# catt.net
KiCad netlist of a schematic drawn in Altium Designer
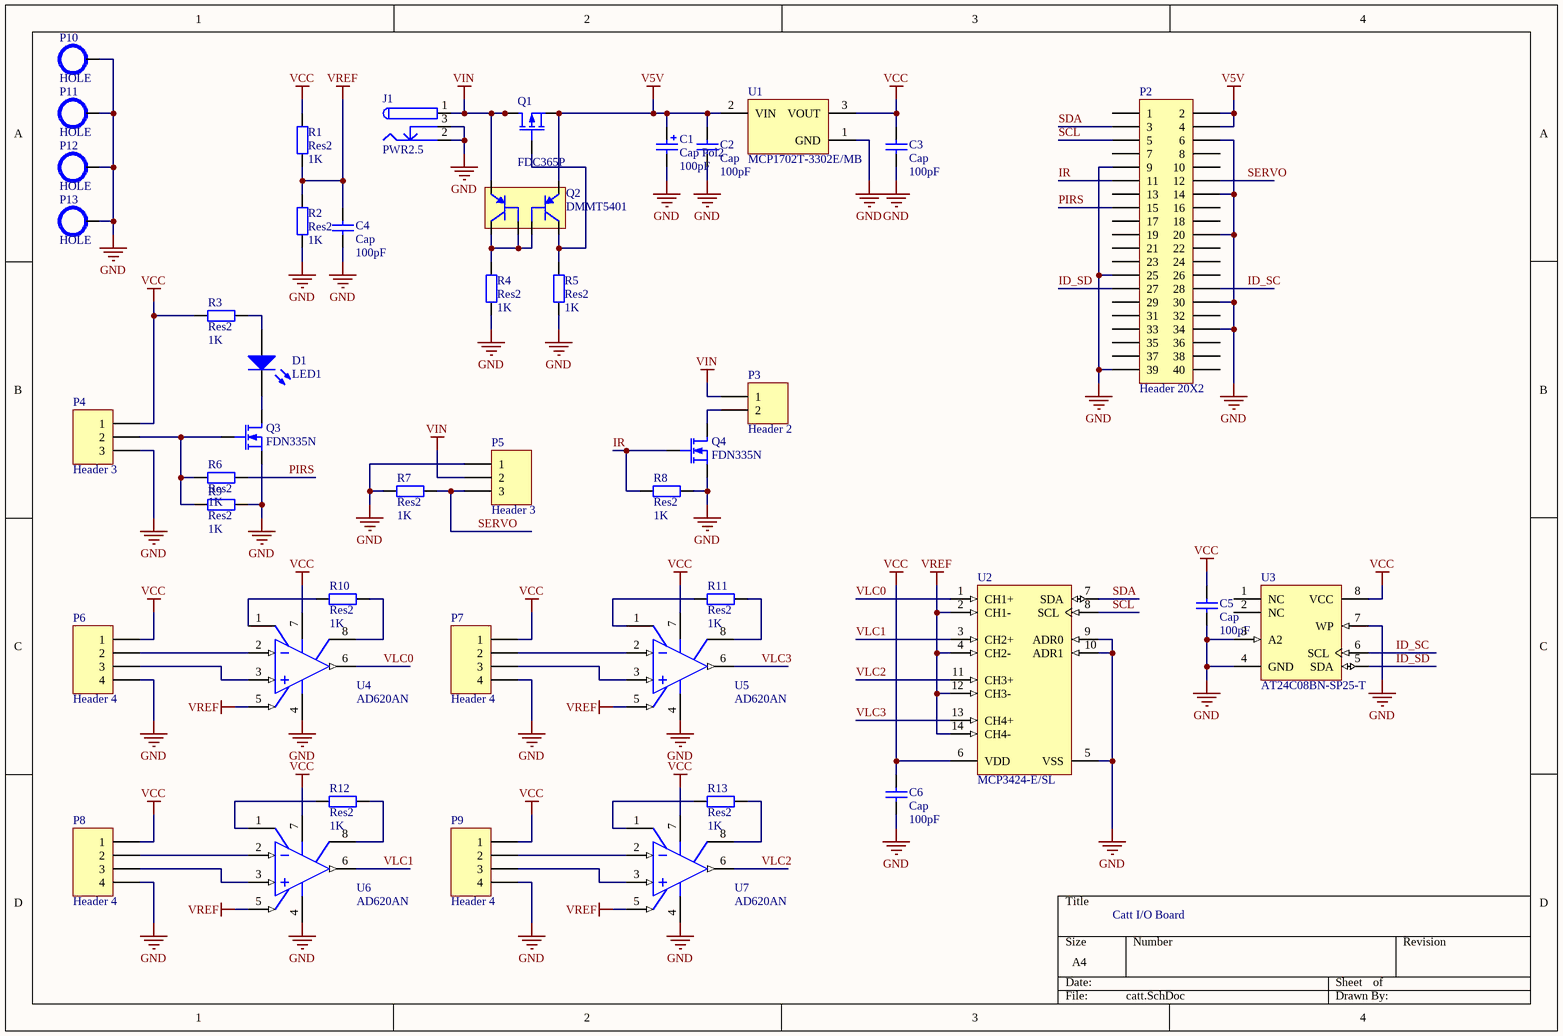
[diagram p0: catt.SchDoc]

(export (version "E")
  (design (tool "Eeschema 10.0.6"))
  (components
    (comp (ref "C1")
      (value "Cap Pol2")
      (footprint "6-0805_N")
      (description "Polarized Capacitor (Axial)")
      (fields (field (name "ALTIUM_VALUE") "100pF") (field (name "PUBLISHER") "Altium Limited"))
      (libsource (lib "Miscellaneous Devices") (part "Cap Pol2"))
    )
    (comp (ref "C2")
      (value "Cap")
      (footprint "1608[0603]")
      (description "Capacitor")
      (fields (field (name "ALTIUM_VALUE") "100pF") (field (name "PUBLISHER") "Altium Limited"))
      (libsource (lib "Miscellaneous Devices") (part "Cap"))
    )
    (comp (ref "C3")
      (value "Cap")
      (footprint "1608[0603]")
      (description "Capacitor")
      (fields (field (name "ALTIUM_VALUE") "100pF") (field (name "PUBLISHER") "Altium Limited"))
      (libsource (lib "Miscellaneous Devices") (part "Cap"))
    )
    (comp (ref "C4")
      (value "Cap")
      (footprint "1608[0603]")
      (description "Capacitor")
      (fields (field (name "ALTIUM_VALUE") "100pF") (field (name "PUBLISHER") "Altium Limited"))
      (libsource (lib "Miscellaneous Devices") (part "Cap"))
    )
    (comp (ref "C5")
      (value "Cap")
      (footprint "1608[0603]")
      (description "Capacitor")
      (fields (field (name "ALTIUM_VALUE") "100pF") (field (name "PUBLISHER") "Altium Limited"))
      (libsource (lib "Miscellaneous Devices") (part "Cap"))
    )
    (comp (ref "C6")
      (value "Cap")
      (footprint "1608[0603]")
      (description "Capacitor")
      (fields (field (name "ALTIUM_VALUE") "100pF") (field (name "PUBLISHER") "Altium Limited"))
      (libsource (lib "Miscellaneous Devices") (part "Cap"))
    )
    (comp (ref "D1")
      (value "LED1")
      (footprint "1608[0603]")
      (description "Typical RED GaAs LED")
      (fields (field (name "PUBLISHER") "Altium Limited"))
      (libsource (lib "Miscellaneous Devices") (part "LED1"))
    )
    (comp (ref "J1")
      (value "PWR2.5")
      (footprint "MJ-180PH")
      (description "Low Voltage Power Supply Connector")
      (fields (field (name "PUBLISHER") "Altium Limited"))
      (libsource (lib "Ed") (part "PWR2.5"))
    )
    (comp (ref "P2")
      (value "Header 20X2")
      (footprint "HDR2X20")
      (description "Header, 20-Pin, Dual row")
      (fields (field (name "PUBLISHER") "Altium Limited"))
      (libsource (lib "Miscellaneous Connectors") (part "Header 20X2"))
    )
    (comp (ref "P3")
      (value "Header 2")
      (footprint "HDR1X2")
      (description "Header, 2-Pin")
      (fields (field (name "PUBLISHER") "Altium Limited"))
      (libsource (lib "Miscellaneous Connectors") (part "Header 2"))
    )
    (comp (ref "P4")
      (value "Header 3")
      (footprint "HDR1X3")
      (description "Header, 3-Pin")
      (fields (field (name "PUBLISHER") "Altium Limited"))
      (libsource (lib "") (part "Header 3_1"))
    )
    (comp (ref "P5")
      (value "Header 3")
      (footprint "HDR1X3")
      (description "Header, 3-Pin")
      (fields (field (name "PUBLISHER") "Altium Limited"))
      (libsource (lib "Miscellaneous Connectors") (part "Header 3"))
    )
    (comp (ref "P6")
      (value "Header 4")
      (footprint "HDR1X4")
      (description "Header, 4-Pin")
      (fields (field (name "PUBLISHER") "Altium Limited"))
      (libsource (lib "Miscellaneous Connectors") (part "Header 4"))
    )
    (comp (ref "P7")
      (value "Header 4")
      (footprint "HDR1X4")
      (description "Header, 4-Pin")
      (fields (field (name "PUBLISHER") "Altium Limited"))
      (libsource (lib "Miscellaneous Connectors") (part "Header 4"))
    )
    (comp (ref "P8")
      (value "Header 4")
      (footprint "HDR1X4")
      (description "Header, 4-Pin")
      (fields (field (name "PUBLISHER") "Altium Limited"))
      (libsource (lib "Miscellaneous Connectors") (part "Header 4"))
    )
    (comp (ref "P9")
      (value "Header 4")
      (footprint "HDR1X4")
      (description "Header, 4-Pin")
      (fields (field (name "PUBLISHER") "Altium Limited"))
      (libsource (lib "Miscellaneous Connectors") (part "Header 4"))
    )
    (comp (ref "P10")
      (value "HOLE")
      (footprint "HOLE")
      (description "Mountiong Hole")
      (libsource (lib "Ed") (part "HOLE"))
    )
    (comp (ref "P11")
      (value "HOLE")
      (footprint "HOLE")
      (description "Mountiong Hole")
      (libsource (lib "Ed") (part "HOLE"))
    )
    (comp (ref "P12")
      (value "HOLE")
      (footprint "HOLE")
      (description "Mountiong Hole")
      (libsource (lib "Ed") (part "HOLE"))
    )
    (comp (ref "P13")
      (value "HOLE")
      (footprint "HOLE")
      (description "Mountiong Hole")
      (libsource (lib "Ed") (part "HOLE"))
    )
    (comp (ref "Q1")
      (value "FDC365P")
      (footprint "SOT23-6")
      (description "P-Channel PowerTrench® MOSFET")
      (fields (field (name "PUBLISHER") "Altium Limited"))
      (libsource (lib "Ed") (part "FDC365P"))
    )
    (comp (ref "Q2")
      (value "DMMT5401")
      (footprint "SOT23-6")
      (description "Matched PNP small signal transistor")
      (fields (field (name "PUBLISHER") "Altium Limited"))
      (libsource (lib "Ed") (part "DMMT5401"))
    )
    (comp (ref "Q3")
      (value "FDN335N")
      (footprint "SOT-23")
      (description "N-Channel MOSFET")
      (fields (field (name "PUBLISHER") "Altium Limited"))
      (libsource (lib "Ed") (part "FDN335N"))
    )
    (comp (ref "Q4")
      (value "FDN335N")
      (footprint "SOT-23")
      (description "N-Channel MOSFET")
      (fields (field (name "PUBLISHER") "Altium Limited"))
      (libsource (lib "Ed") (part "FDN335N"))
    )
    (comp (ref "R1")
      (value "Res2")
      (footprint "J1-0603")
      (description "Resistor")
      (fields (field (name "ALTIUM_VALUE") "1K") (field (name "PUBLISHER") "Altium Limited"))
      (libsource (lib "") (part "Res2_1"))
    )
    (comp (ref "R2")
      (value "Res2")
      (footprint "J1-0603")
      (description "Resistor")
      (fields (field (name "ALTIUM_VALUE") "1K") (field (name "PUBLISHER") "Altium Limited"))
      (libsource (lib "") (part "Res2_1"))
    )
    (comp (ref "R3")
      (value "Res2")
      (footprint "J1-0603")
      (description "Resistor")
      (fields (field (name "ALTIUM_VALUE") "1K") (field (name "PUBLISHER") "Altium Limited"))
      (libsource (lib "Miscellaneous Devices") (part "Res2"))
    )
    (comp (ref "R4")
      (value "Res2")
      (footprint "J1-0603")
      (description "Resistor")
      (fields (field (name "ALTIUM_VALUE") "1K") (field (name "PUBLISHER") "Altium Limited"))
      (libsource (lib "") (part "Res2_1"))
    )
    (comp (ref "R5")
      (value "Res2")
      (footprint "J1-0603")
      (description "Resistor")
      (fields (field (name "ALTIUM_VALUE") "1K") (field (name "PUBLISHER") "Altium Limited"))
      (libsource (lib "") (part "Res2_1"))
    )
    (comp (ref "R6")
      (value "Res2")
      (footprint "J1-0603")
      (description "Resistor")
      (fields (field (name "ALTIUM_VALUE") "1K") (field (name "PUBLISHER") "Altium Limited"))
      (libsource (lib "") (part "Res2_2"))
    )
    (comp (ref "R7")
      (value "Res2")
      (footprint "J1-0603")
      (description "Resistor")
      (fields (field (name "ALTIUM_VALUE") "1K") (field (name "PUBLISHER") "Altium Limited"))
      (libsource (lib "Miscellaneous Devices") (part "Res2"))
    )
    (comp (ref "R8")
      (value "Res2")
      (footprint "J1-0603")
      (description "Resistor")
      (fields (field (name "ALTIUM_VALUE") "1K") (field (name "PUBLISHER") "Altium Limited"))
      (libsource (lib "") (part "Res2_2"))
    )
    (comp (ref "R9")
      (value "Res2")
      (footprint "J1-0603")
      (description "Resistor")
      (fields (field (name "ALTIUM_VALUE") "1K") (field (name "PUBLISHER") "Altium Limited"))
      (libsource (lib "") (part "Res2_2"))
    )
    (comp (ref "R10")
      (value "Res2")
      (footprint "J1-0603")
      (description "Resistor")
      (fields (field (name "ALTIUM_VALUE") "1K") (field (name "PUBLISHER") "Altium Limited"))
      (libsource (lib "Miscellaneous Devices") (part "Res2"))
    )
    (comp (ref "R11")
      (value "Res2")
      (footprint "J1-0603")
      (description "Resistor")
      (fields (field (name "ALTIUM_VALUE") "1K") (field (name "PUBLISHER") "Altium Limited"))
      (libsource (lib "Miscellaneous Devices") (part "Res2"))
    )
    (comp (ref "R12")
      (value "Res2")
      (footprint "J1-0603")
      (description "Resistor")
      (fields (field (name "ALTIUM_VALUE") "1K") (field (name "PUBLISHER") "Altium Limited"))
      (libsource (lib "Miscellaneous Devices") (part "Res2"))
    )
    (comp (ref "R13")
      (value "Res2")
      (footprint "J1-0603")
      (description "Resistor")
      (fields (field (name "ALTIUM_VALUE") "1K") (field (name "PUBLISHER") "Altium Limited"))
      (libsource (lib "Miscellaneous Devices") (part "Res2"))
    )
    (comp (ref "U1")
      (value "MCP1702T-3302E/MB")
      (footprint "SOT-89-MB3_N")
      (description "250 mA Low Quiescent Current LDO Regulator, 3-Pin SOT-89, Extended Temperature, Tape and Reel")
      (fields (field (name "PUBLISHER") "Altium Limited"))
      (libsource (lib "Microchip Power Mgt Line Regulator") (part "MCP1702T-3302E/MB"))
    )
    (comp (ref "U2")
      (value "MCP3424-E/SL")
      (footprint "SOIC-SL14_N")
      (fields (field (name "PUBLISHER") "Altium Limited"))
      (libsource (lib "Microchip Mixed Signal") (part "MCP3424-E/SL"))
    )
    (comp (ref "U3")
      (value "AT24C08BN-SP25-T")
      (footprint "8S1_N")
      (fields (field (name "PUBLISHER") "Altium Limited"))
      (libsource (lib "Atmel Memory Serial EEPROM") (part "AT24C08BN-SP25-T"))
    )
    (comp (ref "U4")
      (value "AD620AN")
      (footprint "SO-8_L")
      (description "Low-Cost, Low-Power Instrumentation Amplifier")
      (fields (field (name "PUBLISHER") "Altium Limited"))
      (libsource (lib "AD Instrumentation Amplifier") (part "AD620AN"))
    )
    (comp (ref "U5")
      (value "AD620AN")
      (footprint "SO-8_L")
      (description "Low-Cost, Low-Power Instrumentation Amplifier")
      (fields (field (name "PUBLISHER") "Altium Limited"))
      (libsource (lib "AD Instrumentation Amplifier") (part "AD620AN"))
    )
    (comp (ref "U6")
      (value "AD620AN")
      (footprint "SO-8_L")
      (description "Low-Cost, Low-Power Instrumentation Amplifier")
      (fields (field (name "PUBLISHER") "Altium Limited"))
      (libsource (lib "AD Instrumentation Amplifier") (part "AD620AN"))
    )
    (comp (ref "U7")
      (value "AD620AN")
      (footprint "SO-8_L")
      (description "Low-Cost, Low-Power Instrumentation Amplifier")
      (fields (field (name "PUBLISHER") "Altium Limited"))
      (libsource (lib "AD Instrumentation Amplifier") (part "AD620AN"))
    )
  )
  (nets
    (net (code "1") (name "/ID_SC") (class "Default")
      (node (ref "P2") (pin "28") (pinfunction "28_28") (pintype "passive"))
      (node (ref "U3") (pin "6") (pinfunction "SCL_6") (pintype "input"))
    )
    (net (code "2") (name "/ID_SD") (class "Default")
      (node (ref "P2") (pin "27") (pinfunction "27_27") (pintype "passive"))
      (node (ref "U3") (pin "5") (pinfunction "SDA_5") (pintype "bidirectional"))
    )
    (net (code "3") (name "/IR") (class "Default")
      (node (ref "P2") (pin "11") (pinfunction "11_11") (pintype "passive"))
      (node (ref "Q4") (pin "1") (pinfunction "G_1") (pintype "passive"))
      (node (ref "R8") (pin "1") (pinfunction "1_1") (pintype "passive"))
    )
    (net (code "4") (name "/PIRS") (class "Default")
      (node (ref "P2") (pin "15") (pinfunction "15_15") (pintype "passive"))
      (node (ref "R6") (pin "2") (pinfunction "2_2") (pintype "passive"))
    )
    (net (code "5") (name "/SCL") (class "Default")
      (node (ref "P2") (pin "5") (pinfunction "5_5") (pintype "passive"))
      (node (ref "U2") (pin "8") (pinfunction "SCL_8") (pintype "input"))
    )
    (net (code "6") (name "/SDA") (class "Default")
      (node (ref "P2") (pin "3") (pinfunction "3_3") (pintype "passive"))
      (node (ref "U2") (pin "7") (pinfunction "SDA_7") (pintype "bidirectional"))
    )
    (net (code "7") (name "/SERVO") (class "Default")
      (node (ref "P2") (pin "12") (pinfunction "12_12") (pintype "passive"))
      (node (ref "P5") (pin "3") (pinfunction "3_3") (pintype "passive"))
      (node (ref "R7") (pin "1") (pinfunction "1_1") (pintype "passive"))
    )
    (net (code "8") (name "/VLC0") (class "Default")
      (node (ref "U2") (pin "1") (pinfunction "CH1+_1") (pintype "input"))
      (node (ref "U4") (pin "6") (pinfunction "OUT_6") (pintype "output"))
    )
    (net (code "9") (name "/VLC1") (class "Default")
      (node (ref "U2") (pin "3") (pinfunction "CH2+_3") (pintype "input"))
      (node (ref "U6") (pin "6") (pinfunction "OUT_6") (pintype "output"))
    )
    (net (code "10") (name "/VLC2") (class "Default")
      (node (ref "U2") (pin "11") (pinfunction "CH3+_11") (pintype "input"))
      (node (ref "U7") (pin "6") (pinfunction "OUT_6") (pintype "output"))
    )
    (net (code "11") (name "/VLC3") (class "Default")
      (node (ref "U2") (pin "13") (pinfunction "CH4+_13") (pintype "input"))
      (node (ref "U5") (pin "6") (pinfunction "OUT_6") (pintype "output"))
    )
    (net (code "12") (name "GND") (class "Default")
      (node (ref "C1") (pin "2") (pinfunction "2_2") (pintype "passive"))
      (node (ref "C2") (pin "1") (pinfunction "1_1") (pintype "passive"))
      (node (ref "C3") (pin "1") (pinfunction "1_1") (pintype "passive"))
      (node (ref "C4") (pin "1") (pinfunction "1_1") (pintype "passive"))
      (node (ref "C5") (pin "1") (pinfunction "1_1") (pintype "passive"))
      (node (ref "C6") (pin "1") (pinfunction "1_1") (pintype "passive"))
      (node (ref "J1") (pin "2") (pinfunction "2_2") (pintype "power_in"))
      (node (ref "J1") (pin "3") (pinfunction "3_3") (pintype "power_in"))
      (node (ref "P10") (pin "0") (pinfunction "0_0") (pintype "passive"))
      (node (ref "P11") (pin "0") (pinfunction "0_0") (pintype "passive"))
      (node (ref "P12") (pin "0") (pinfunction "0_0") (pintype "passive"))
      (node (ref "P13") (pin "0") (pinfunction "0_0") (pintype "passive"))
      (node (ref "P2") (pin "14") (pinfunction "14_14") (pintype "passive"))
      (node (ref "P2") (pin "20") (pinfunction "20_20") (pintype "passive"))
      (node (ref "P2") (pin "25") (pinfunction "25_25") (pintype "passive"))
      (node (ref "P2") (pin "30") (pinfunction "30_30") (pintype "passive"))
      (node (ref "P2") (pin "34") (pinfunction "34_34") (pintype "passive"))
      (node (ref "P2") (pin "39") (pinfunction "39_39") (pintype "passive"))
      (node (ref "P2") (pin "6") (pinfunction "6_6") (pintype "passive"))
      (node (ref "P2") (pin "9") (pinfunction "9_9") (pintype "passive"))
      (node (ref "P4") (pin "3") (pinfunction "3_3") (pintype "passive"))
      (node (ref "P5") (pin "1") (pinfunction "1_1") (pintype "passive"))
      (node (ref "P6") (pin "4") (pinfunction "4_4") (pintype "passive"))
      (node (ref "P7") (pin "4") (pinfunction "4_4") (pintype "passive"))
      (node (ref "P8") (pin "4") (pinfunction "4_4") (pintype "passive"))
      (node (ref "P9") (pin "4") (pinfunction "4_4") (pintype "passive"))
      (node (ref "Q3") (pin "2") (pinfunction "S_2") (pintype "passive"))
      (node (ref "Q4") (pin "2") (pinfunction "S_2") (pintype "passive"))
      (node (ref "R2") (pin "1") (pinfunction "1_1") (pintype "passive"))
      (node (ref "R4") (pin "1") (pinfunction "1_1") (pintype "passive"))
      (node (ref "R5") (pin "1") (pinfunction "1_1") (pintype "passive"))
      (node (ref "R7") (pin "2") (pinfunction "2_2") (pintype "passive"))
      (node (ref "R8") (pin "2") (pinfunction "2_2") (pintype "passive"))
      (node (ref "R9") (pin "2") (pinfunction "2_2") (pintype "passive"))
      (node (ref "U1") (pin "1") (pinfunction "GND_1") (pintype "power_in"))
      (node (ref "U2") (pin "10") (pinfunction "ADR1_10") (pintype "input"))
      (node (ref "U2") (pin "5") (pinfunction "VSS_5") (pintype "power_in"))
      (node (ref "U2") (pin "9") (pinfunction "ADR0_9") (pintype "input"))
      (node (ref "U3") (pin "3") (pinfunction "A2_3") (pintype "input"))
      (node (ref "U3") (pin "4") (pinfunction "GND_4") (pintype "power_in"))
      (node (ref "U3") (pin "7") (pinfunction "WP_7") (pintype "input"))
      (node (ref "U4") (pin "4") (pinfunction "V-_4") (pintype "power_in"))
      (node (ref "U5") (pin "4") (pinfunction "V-_4") (pintype "power_in"))
      (node (ref "U6") (pin "4") (pinfunction "V-_4") (pintype "power_in"))
      (node (ref "U7") (pin "4") (pinfunction "V-_4") (pintype "power_in"))
    )
    (net (code "13") (name "Net-(D1-A)") (class "Default")
      (node (ref "D1") (pin "1") (pinfunction "A_1") (pintype "passive"))
      (node (ref "R3") (pin "1") (pinfunction "1_1") (pintype "passive"))
    )
    (net (code "14") (name "Net-(D1-K)") (class "Default")
      (node (ref "D1") (pin "2") (pinfunction "K_2") (pintype "passive"))
      (node (ref "Q3") (pin "3") (pinfunction "D_3") (pintype "passive"))
    )
    (net (code "15") (name "Net-(Q1-G)") (class "Default")
      (node (ref "Q1") (pin "3") (pinfunction "G_3") (pintype "passive"))
      (node (ref "Q2") (pin "4") (pinfunction "C2_4") (pintype "passive"))
      (node (ref "R5") (pin "2") (pinfunction "2_2") (pintype "passive"))
    )
    (net (code "16") (name "Net-(Q2-B1)") (class "Default")
      (node (ref "Q2") (pin "1") (pinfunction "C1_1") (pintype "passive"))
      (node (ref "Q2") (pin "2") (pinfunction "B1_2") (pintype "passive"))
      (node (ref "Q2") (pin "3") (pinfunction "B2_3") (pintype "passive"))
      (node (ref "R4") (pin "2") (pinfunction "2_2") (pintype "passive"))
    )
    (net (code "17") (name "Net-(Q3-G)") (class "Default")
      (node (ref "P4") (pin "2") (pinfunction "2_2") (pintype "passive"))
      (node (ref "Q3") (pin "1") (pinfunction "G_1") (pintype "passive"))
      (node (ref "R6") (pin "1") (pinfunction "1_1") (pintype "passive"))
      (node (ref "R9") (pin "1") (pinfunction "1_1") (pintype "passive"))
    )
    (net (code "18") (name "Net-(Q4-D)") (class "Default")
      (node (ref "P3") (pin "2") (pinfunction "2_2") (pintype "passive"))
      (node (ref "Q4") (pin "3") (pinfunction "D_3") (pintype "passive"))
    )
    (net (code "19") (name "Net-(R10-Pad1)") (class "Default")
      (node (ref "R10") (pin "1") (pinfunction "1_1") (pintype "passive"))
      (node (ref "U4") (pin "8") (pinfunction "RG_8") (pintype "passive"))
    )
    (net (code "20") (name "Net-(R10-Pad2)") (class "Default")
      (node (ref "R10") (pin "2") (pinfunction "2_2") (pintype "passive"))
      (node (ref "U4") (pin "1") (pinfunction "RG_1") (pintype "passive"))
    )
    (net (code "21") (name "Net-(R11-Pad1)") (class "Default")
      (node (ref "R11") (pin "1") (pinfunction "1_1") (pintype "passive"))
      (node (ref "U5") (pin "8") (pinfunction "RG_8") (pintype "passive"))
    )
    (net (code "22") (name "Net-(R11-Pad2)") (class "Default")
      (node (ref "R11") (pin "2") (pinfunction "2_2") (pintype "passive"))
      (node (ref "U5") (pin "1") (pinfunction "RG_1") (pintype "passive"))
    )
    (net (code "23") (name "Net-(R12-Pad1)") (class "Default")
      (node (ref "R12") (pin "1") (pinfunction "1_1") (pintype "passive"))
      (node (ref "U6") (pin "8") (pinfunction "RG_8") (pintype "passive"))
    )
    (net (code "24") (name "Net-(R12-Pad2)") (class "Default")
      (node (ref "R12") (pin "2") (pinfunction "2_2") (pintype "passive"))
      (node (ref "U6") (pin "1") (pinfunction "RG_1") (pintype "passive"))
    )
    (net (code "25") (name "Net-(R13-Pad1)") (class "Default")
      (node (ref "R13") (pin "1") (pinfunction "1_1") (pintype "passive"))
      (node (ref "U7") (pin "8") (pinfunction "RG_8") (pintype "passive"))
    )
    (net (code "26") (name "Net-(R13-Pad2)") (class "Default")
      (node (ref "R13") (pin "2") (pinfunction "2_2") (pintype "passive"))
      (node (ref "U7") (pin "1") (pinfunction "RG_1") (pintype "passive"))
    )
    (net (code "27") (name "Net-(U4-+IN)") (class "Default")
      (node (ref "P6") (pin "3") (pinfunction "3_3") (pintype "passive"))
      (node (ref "U4") (pin "3") (pinfunction "+IN_3") (pintype "input"))
    )
    (net (code "28") (name "Net-(U4--IN)") (class "Default")
      (node (ref "P6") (pin "2") (pinfunction "2_2") (pintype "passive"))
      (node (ref "U4") (pin "2") (pinfunction "-IN_2") (pintype "input"))
    )
    (net (code "29") (name "Net-(U5-+IN)") (class "Default")
      (node (ref "P7") (pin "3") (pinfunction "3_3") (pintype "passive"))
      (node (ref "U5") (pin "3") (pinfunction "+IN_3") (pintype "input"))
    )
    (net (code "30") (name "Net-(U5--IN)") (class "Default")
      (node (ref "P7") (pin "2") (pinfunction "2_2") (pintype "passive"))
      (node (ref "U5") (pin "2") (pinfunction "-IN_2") (pintype "input"))
    )
    (net (code "31") (name "Net-(U6-+IN)") (class "Default")
      (node (ref "P8") (pin "3") (pinfunction "3_3") (pintype "passive"))
      (node (ref "U6") (pin "3") (pinfunction "+IN_3") (pintype "input"))
    )
    (net (code "32") (name "Net-(U6--IN)") (class "Default")
      (node (ref "P8") (pin "2") (pinfunction "2_2") (pintype "passive"))
      (node (ref "U6") (pin "2") (pinfunction "-IN_2") (pintype "input"))
    )
    (net (code "33") (name "Net-(U7-+IN)") (class "Default")
      (node (ref "P9") (pin "3") (pinfunction "3_3") (pintype "passive"))
      (node (ref "U7") (pin "3") (pinfunction "+IN_3") (pintype "input"))
    )
    (net (code "34") (name "Net-(U7--IN)") (class "Default")
      (node (ref "P9") (pin "2") (pinfunction "2_2") (pintype "passive"))
      (node (ref "U7") (pin "2") (pinfunction "-IN_2") (pintype "input"))
    )
    (net (code "35") (name "V5V") (class "Default")
      (node (ref "C1") (pin "1") (pinfunction "1_1") (pintype "passive"))
      (node (ref "C2") (pin "2") (pinfunction "2_2") (pintype "passive"))
      (node (ref "P2") (pin "2") (pinfunction "2_2") (pintype "passive"))
      (node (ref "P2") (pin "4") (pinfunction "4_4") (pintype "passive"))
      (node (ref "Q1") (pin "4") (pinfunction "S_4") (pintype "passive"))
      (node (ref "Q2") (pin "5") (pinfunction "E2_5") (pintype "passive"))
      (node (ref "U1") (pin "2") (pinfunction "VIN_2") (pintype "power_in"))
    )
    (net (code "36") (name "VCC") (class "Default")
      (node (ref "C3") (pin "2") (pinfunction "2_2") (pintype "passive"))
      (node (ref "C5") (pin "2") (pinfunction "2_2") (pintype "passive"))
      (node (ref "C6") (pin "2") (pinfunction "2_2") (pintype "passive"))
      (node (ref "P4") (pin "1") (pinfunction "1_1") (pintype "passive"))
      (node (ref "P6") (pin "1") (pinfunction "1_1") (pintype "passive"))
      (node (ref "P7") (pin "1") (pinfunction "1_1") (pintype "passive"))
      (node (ref "P8") (pin "1") (pinfunction "1_1") (pintype "passive"))
      (node (ref "P9") (pin "1") (pinfunction "1_1") (pintype "passive"))
      (node (ref "R1") (pin "2") (pinfunction "2_2") (pintype "passive"))
      (node (ref "R3") (pin "2") (pinfunction "2_2") (pintype "passive"))
      (node (ref "U1") (pin "3") (pinfunction "VOUT_3") (pintype "power_in"))
      (node (ref "U2") (pin "6") (pinfunction "VDD_6") (pintype "power_in"))
      (node (ref "U3") (pin "8") (pinfunction "VCC_8") (pintype "power_in"))
      (node (ref "U4") (pin "7") (pinfunction "V+_7") (pintype "power_in"))
      (node (ref "U5") (pin "7") (pinfunction "V+_7") (pintype "power_in"))
      (node (ref "U6") (pin "7") (pinfunction "V+_7") (pintype "power_in"))
      (node (ref "U7") (pin "7") (pinfunction "V+_7") (pintype "power_in"))
    )
    (net (code "37") (name "VIN") (class "Default")
      (node (ref "J1") (pin "1") (pinfunction "1_1") (pintype "power_in"))
      (node (ref "P3") (pin "1") (pinfunction "1_1") (pintype "passive"))
      (node (ref "P5") (pin "2") (pinfunction "2_2") (pintype "passive"))
      (node (ref "Q1") (pin "1") (pinfunction "D_1") (pintype "passive"))
      (node (ref "Q1") (pin "2") (pinfunction "D_2") (pintype "passive"))
      (node (ref "Q1") (pin "5") (pinfunction "D_5") (pintype "passive"))
      (node (ref "Q1") (pin "6") (pinfunction "D_6") (pintype "passive"))
      (node (ref "Q2") (pin "6") (pinfunction "E1_6") (pintype "passive"))
    )
    (net (code "38") (name "VREF") (class "Default")
      (node (ref "C4") (pin "2") (pinfunction "2_2") (pintype "passive"))
      (node (ref "R1") (pin "1") (pinfunction "1_1") (pintype "passive"))
      (node (ref "R2") (pin "2") (pinfunction "2_2") (pintype "passive"))
      (node (ref "U2") (pin "12") (pinfunction "CH3-_12") (pintype "input"))
      (node (ref "U2") (pin "14") (pinfunction "CH4-_14") (pintype "input"))
      (node (ref "U2") (pin "2") (pinfunction "CH1-_2") (pintype "input"))
      (node (ref "U2") (pin "4") (pinfunction "CH2-_4") (pintype "input"))
      (node (ref "U4") (pin "5") (pinfunction "REF_5") (pintype "input"))
      (node (ref "U5") (pin "5") (pinfunction "REF_5") (pintype "input"))
      (node (ref "U6") (pin "5") (pinfunction "REF_5") (pintype "input"))
      (node (ref "U7") (pin "5") (pinfunction "REF_5") (pintype "input"))
    )
    (net (code "39") (name "unconnected-(P2-Pad1)") (class "Default")
      (node (ref "P2") (pin "1") (pinfunction "1_1") (pintype "passive"))
    )
    (net (code "40") (name "unconnected-(P2-Pad7)") (class "Default")
      (node (ref "P2") (pin "7") (pinfunction "7_7") (pintype "passive"))
    )
    (net (code "41") (name "unconnected-(P2-Pad8)") (class "Default")
      (node (ref "P2") (pin "8") (pinfunction "8_8") (pintype "passive"))
    )
    (net (code "42") (name "unconnected-(P2-Pad10)") (class "Default")
      (node (ref "P2") (pin "10") (pinfunction "10_10") (pintype "passive"))
    )
    (net (code "43") (name "unconnected-(P2-Pad13)") (class "Default")
      (node (ref "P2") (pin "13") (pinfunction "13_13") (pintype "passive"))
    )
    (net (code "44") (name "unconnected-(P2-Pad16)") (class "Default")
      (node (ref "P2") (pin "16") (pinfunction "16_16") (pintype "passive"))
    )
    (net (code "45") (name "unconnected-(P2-Pad17)") (class "Default")
      (node (ref "P2") (pin "17") (pinfunction "17_17") (pintype "passive"))
    )
    (net (code "46") (name "unconnected-(P2-Pad18)") (class "Default")
      (node (ref "P2") (pin "18") (pinfunction "18_18") (pintype "passive"))
    )
    (net (code "47") (name "unconnected-(P2-Pad19)") (class "Default")
      (node (ref "P2") (pin "19") (pinfunction "19_19") (pintype "passive"))
    )
    (net (code "48") (name "unconnected-(P2-Pad21)") (class "Default")
      (node (ref "P2") (pin "21") (pinfunction "21_21") (pintype "passive"))
    )
    (net (code "49") (name "unconnected-(P2-Pad22)") (class "Default")
      (node (ref "P2") (pin "22") (pinfunction "22_22") (pintype "passive"))
    )
    (net (code "50") (name "unconnected-(P2-Pad23)") (class "Default")
      (node (ref "P2") (pin "23") (pinfunction "23_23") (pintype "passive"))
    )
    (net (code "51") (name "unconnected-(P2-Pad24)") (class "Default")
      (node (ref "P2") (pin "24") (pinfunction "24_24") (pintype "passive"))
    )
    (net (code "52") (name "unconnected-(P2-Pad26)") (class "Default")
      (node (ref "P2") (pin "26") (pinfunction "26_26") (pintype "passive"))
    )
    (net (code "53") (name "unconnected-(P2-Pad29)") (class "Default")
      (node (ref "P2") (pin "29") (pinfunction "29_29") (pintype "passive"))
    )
    (net (code "54") (name "unconnected-(P2-Pad31)") (class "Default")
      (node (ref "P2") (pin "31") (pinfunction "31_31") (pintype "passive"))
    )
    (net (code "55") (name "unconnected-(P2-Pad32)") (class "Default")
      (node (ref "P2") (pin "32") (pinfunction "32_32") (pintype "passive"))
    )
    (net (code "56") (name "unconnected-(P2-Pad33)") (class "Default")
      (node (ref "P2") (pin "33") (pinfunction "33_33") (pintype "passive"))
    )
    (net (code "57") (name "unconnected-(P2-Pad35)") (class "Default")
      (node (ref "P2") (pin "35") (pinfunction "35_35") (pintype "passive"))
    )
    (net (code "58") (name "unconnected-(P2-Pad36)") (class "Default")
      (node (ref "P2") (pin "36") (pinfunction "36_36") (pintype "passive"))
    )
    (net (code "59") (name "unconnected-(P2-Pad37)") (class "Default")
      (node (ref "P2") (pin "37") (pinfunction "37_37") (pintype "passive"))
    )
    (net (code "60") (name "unconnected-(P2-Pad38)") (class "Default")
      (node (ref "P2") (pin "38") (pinfunction "38_38") (pintype "passive"))
    )
    (net (code "61") (name "unconnected-(P2-Pad40)") (class "Default")
      (node (ref "P2") (pin "40") (pinfunction "40_40") (pintype "passive"))
    )
    (net (code "62") (name "unconnected-(U3-NC-Pad1)") (class "Default")
      (node (ref "U3") (pin "1") (pinfunction "NC_1") (pintype "passive"))
    )
    (net (code "63") (name "unconnected-(U3-NC-Pad2)") (class "Default")
      (node (ref "U3") (pin "2") (pinfunction "NC_2") (pintype "passive"))
    )
  )
)
